# NiXie_tube_clock.net
KiCad netlist of a schematic drawn in Altium Designer
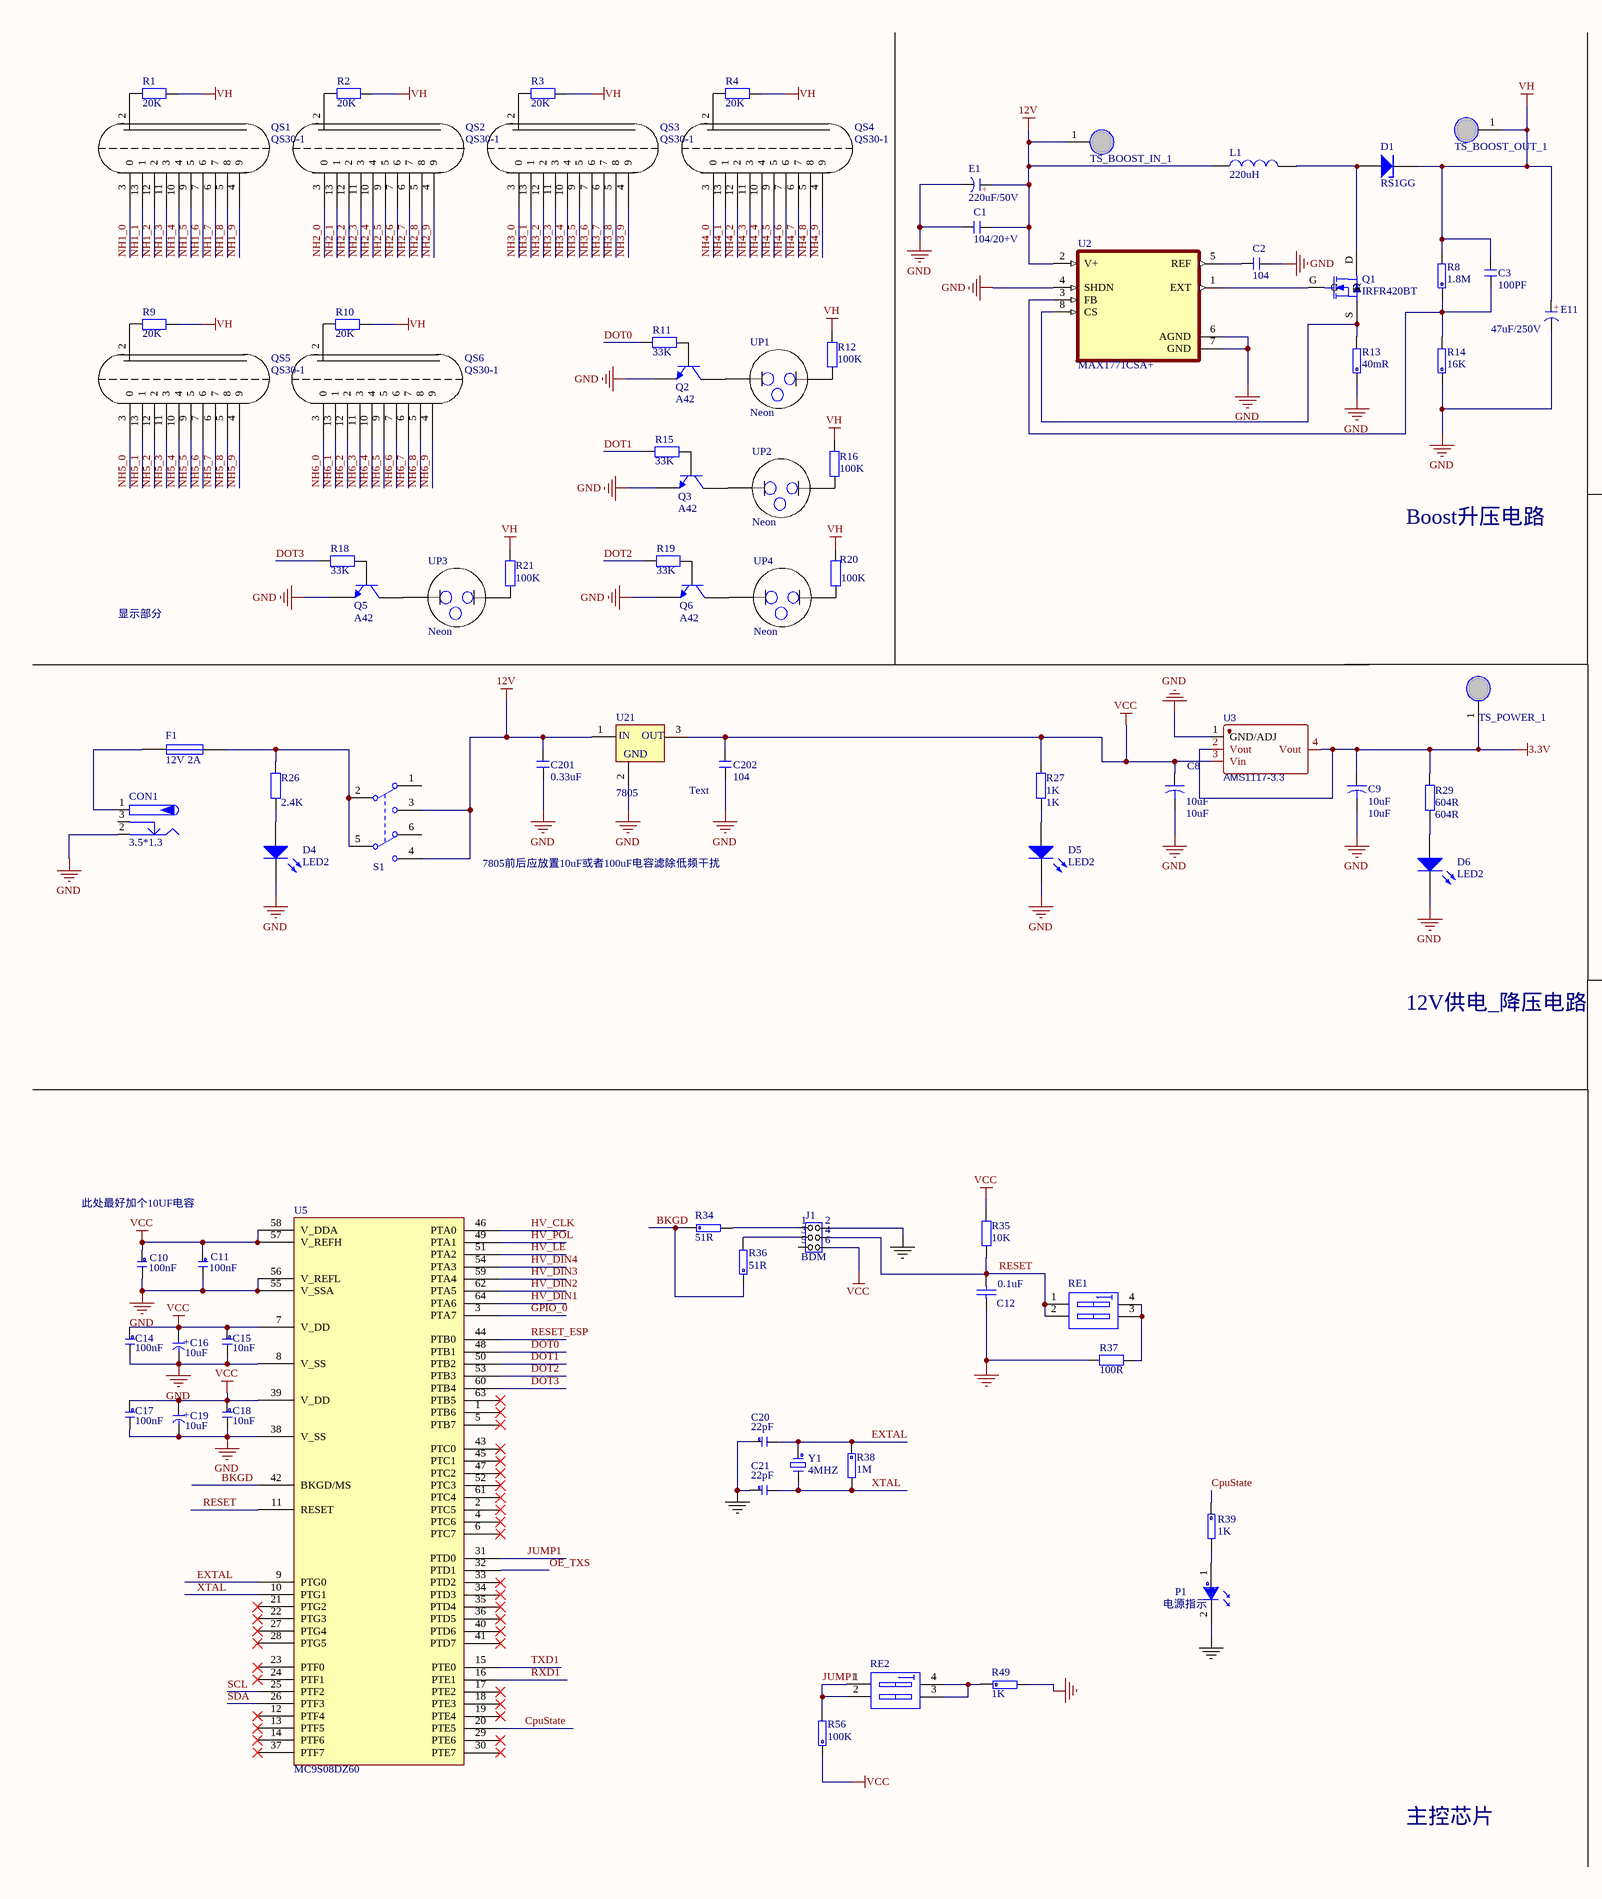
[diagram p0: NiXie_tube_clock.SchDoc, left]
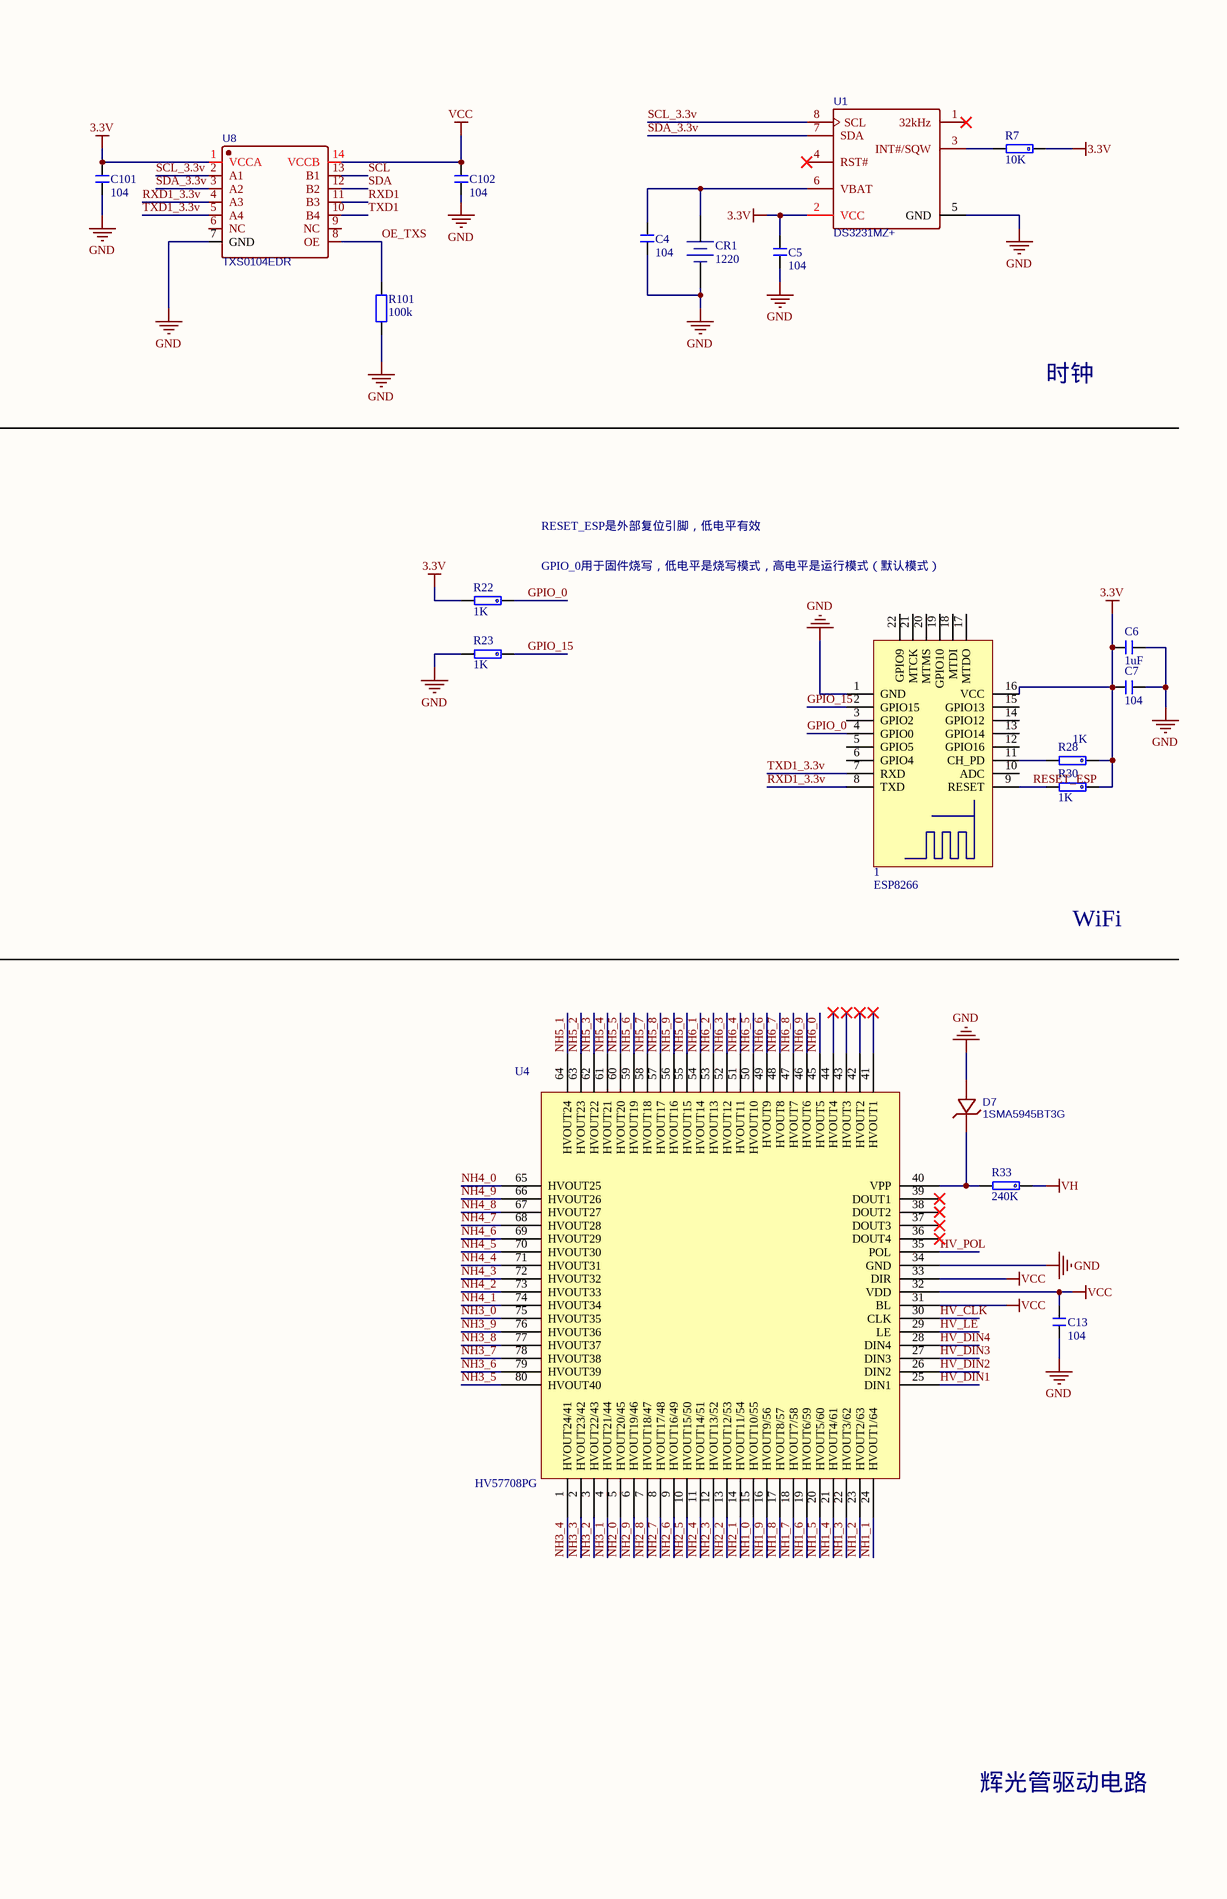
[diagram p1: NiXie_tube_clock.SchDoc, right]

(export (version "E")
  (design (tool "Eeschema 10.0.6"))
  (components
    (comp (ref "1") (value "ESP8266") (footprint "ESP8266") (libsource (lib "ESP8266V1.2") (part "ESP8266")))
    (comp (ref "C1")
      (value "104/20+V")
      (footprint "C 0805_L")
      (description "贴片电容")
      (libsource (lib "0.1 - 电阻-电容-电感") (part "C"))
    )
    (comp (ref "C2")
      (value "104")
      (footprint "C 0805_L")
      (description "贴片电容")
      (libsource (lib "0.1 - 电阻-电容-电感") (part "C"))
    )
    (comp (ref "C3")
      (value "100PF")
      (footprint "C 0805_L")
      (description "贴片电容")
      (libsource (lib "0.1 - 电阻-电容-电感") (part "C"))
    )
    (comp (ref "C4")
      (value "104")
      (footprint "C 0805_L")
      (description "贴片电容")
      (libsource (lib "0.1 - 电阻-电容-电感") (part "C"))
    )
    (comp (ref "C5")
      (value "104")
      (footprint "C 0805_L")
      (description "贴片电容")
      (libsource (lib "0.1 - 电阻-电容-电感") (part "C"))
    )
    (comp (ref "C6")
      (value "1uF")
      (footprint "C 0805_L")
      (description "贴片电容")
      (libsource (lib "0.1 - 电阻-电容-电感") (part "C"))
    )
    (comp (ref "C7")
      (value "104")
      (footprint "C 0805_L")
      (description "贴片电容")
      (libsource (lib "0.1 - 电阻-电容-电感") (part "C"))
    )
    (comp (ref "C8")
      (value "10uF")
      (footprint "CD B(3528)")
      (description "钽电容")
      (fields (field (name "ALTIUM_VALUE") "10uF") (field (name "PUBLISHER") "Altium Limited"))
      (libsource (lib "Miscellaneous Devices") (part "Cap2"))
    )
    (comp (ref "C9")
      (value "10uF")
      (footprint "CD B(3528)")
      (description "钽电容")
      (fields (field (name "ALTIUM_VALUE") "10uF") (field (name "PUBLISHER") "Altium Limited"))
      (libsource (lib "Miscellaneous Devices") (part "Cap2"))
    )
    (comp (ref "C10") (value "100nF") (footprint "R 0805_L") (libsource (lib "*") (part "CAP")))
    (comp (ref "C11") (value "100nF") (footprint "R 0805_L") (libsource (lib "*") (part "CAP")))
    (comp (ref "C12")
      (value "0.1uF")
      (footprint "R 0805_L")
      (description "Capacitor")
      (fields (field (name "PUBLISHER") "Altium Limited"))
      (libsource (lib "Miscellaneous Devices") (part "Cap"))
    )
    (comp (ref "C13")
      (value "104")
      (footprint "C 0805_L")
      (description "贴片电容")
      (libsource (lib "0.1 - 电阻-电容-电感") (part "C"))
    )
    (comp (ref "C14") (value "100nF") (footprint "R 0805_L") (libsource (lib "*") (part "CAP")))
    (comp (ref "C15") (value "10nF") (footprint "R 0805_L") (libsource (lib "*") (part "CAP")))
    (comp (ref "C16") (value "10uF") (footprint "CD B(3528)") (libsource (lib "*") (part "ELE-CAP")))
    (comp (ref "C17") (value "100nF") (footprint "R 0805_L") (libsource (lib "*") (part "CAP")))
    (comp (ref "C18") (value "10nF") (footprint "R 0805_L") (libsource (lib "*") (part "CAP")))
    (comp (ref "C19") (value "10uF") (footprint "CD B(3528)") (libsource (lib "*") (part "ELE-CAP")))
    (comp (ref "C20") (value "22pF") (footprint "R 0805_L") (libsource (lib "*") (part "CAP")))
    (comp (ref "C21") (value "22pF") (footprint "R 0805_L") (libsource (lib "*") (part "CAP")))
    (comp (ref "C101")
      (value "104")
      (footprint "C 0805_L")
      (description "贴片电容")
      (libsource (lib "0.1 - 电阻-电容-电感") (part "C"))
    )
    (comp (ref "C102")
      (value "104")
      (footprint "C 0805_L")
      (description "贴片电容")
      (libsource (lib "0.1 - 电阻-电容-电感") (part "C"))
    )
    (comp (ref "C201")
      (value "0.33uF")
      (footprint "C 0805_L")
      (description "贴片电容")
      (libsource (lib "0.1 - 电阻-电容-电感") (part "C"))
    )
    (comp (ref "C202")
      (value "104")
      (footprint "C 0805_L")
      (description "贴片电容")
      (libsource (lib "0.1 - 电阻-电容-电感") (part "C"))
    )
    (comp (ref "CON1")
      (value "3.5*1.3")
      (footprint "DC-005")
      (description "低压电源接口")
      (libsource (lib "0.8 - 以太网-音频-USB插座") (part "P-DC"))
    )
    (comp (ref "CR1")
      (value "1220")
      (footprint "CR1220_A")
      (description "微型电池")
      (libsource (lib "0.7 - 常用按键-开关-蜂鸣器-电池") (part "CR-3V"))
    )
    (comp (ref "D1")
      (value "RS1GG")
      (footprint "SMA")
      (description "Zener Diode")
      (libsource (lib "0.2 - 二极管-整流桥") (part "稳压二极管"))
    )
    (comp (ref "D4")
      (value "LED2")
      (footprint "LED 0805G")
      (description "Typical RED, GREEN, YELLOW, AMBER GaAs LED")
      (fields (field (name "PUBLISHER") "Altium Limited"))
      (libsource (lib "Miscellaneous Devices") (part "LED2"))
    )
    (comp (ref "D5")
      (value "LED2")
      (footprint "LED 0805G")
      (description "Typical RED, GREEN, YELLOW, AMBER GaAs LED")
      (fields (field (name "PUBLISHER") "Altium Limited"))
      (libsource (lib "Miscellaneous Devices") (part "LED2"))
    )
    (comp (ref "D6")
      (value "LED2")
      (footprint "LED 0805G")
      (description "Typical RED, GREEN, YELLOW, AMBER GaAs LED")
      (fields (field (name "PUBLISHER") "Altium Limited"))
      (libsource (lib "Miscellaneous Devices") (part "LED2"))
    )
    (comp (ref "D7")
      (value "1SMA5945BT3G")
      (footprint "SMA")
      (fields
        (field (name "BOM_SUPPLIER PART") "C94872")
        (field (name "BOM_MANUFACTURER PART") "1SMA5931BT3G")
        (field (name "CONTRIBUTOR") "LCSC")
      )
      (libsource (lib "ISMA5913BT3G") (part "1SMA5931BT3G"))
    )
    (comp (ref "E1")
      (value "220uF/50V")
      (footprint "CT 10*8 - C")
      (description "贴片固态电容")
      (libsource (lib "") (part "CS_SMD_1"))
    )
    (comp (ref "E11")
      (value "47uF/250V")
      (footprint "CAP 5.0*12.5*20")
      (description "贴片固态电容")
      (libsource (lib "0.1 - 电阻-电容-电感") (part "CS_SMD"))
    )
    (comp (ref "F1")
      (value "12V 2A")
      (footprint "FU 1206")
      (description "Fuse")
      (fields (field (name "PUBLISHER") "Altium Limited"))
      (libsource (lib "Miscellaneous Devices") (part "Fuse 1"))
    )
    (comp (ref "J1") (value "BDM") (footprint "PIN6") (libsource (lib "*") (part "BDM")))
    (comp (ref "L1")
      (value "220uH")
      (footprint "CDRH129")
      (description "小功率贴片电感")
      (libsource (lib "0.1 - 电阻-电容-电感") (part "L"))
    )
    (comp (ref "P1") (value "电源指示") (footprint "LED 0805R") (libsource (lib "*") (part "LED")))
    (comp (ref "Q1")
      (value "IRFR420BT")
      (footprint "TO252")
      (description "N-Channel MOSFET")
      (libsource (lib "0.4 - 三极管-场效应管-可控硅") (part "MOSFET-N"))
    )
    (comp (ref "Q2")
      (value "A42")
      (footprint "SOT23")
      (description "NPN General Purpose Amplifier")
      (fields (field (name "PUBLISHER") "Altium Limited"))
      (libsource (lib "Miscellaneous Devices") (part "2N3904"))
    )
    (comp (ref "Q3")
      (value "A42")
      (footprint "SOT-23")
      (description "NPN General Purpose Amplifier")
      (fields (field (name "PUBLISHER") "Altium Limited"))
      (libsource (lib "Miscellaneous Devices") (part "2N3904"))
    )
    (comp (ref "Q5")
      (value "A42")
      (footprint "SOT-23")
      (description "NPN General Purpose Amplifier")
      (fields (field (name "PUBLISHER") "Altium Limited"))
      (libsource (lib "Miscellaneous Devices") (part "2N3904"))
    )
    (comp (ref "Q6")
      (value "A42")
      (footprint "SOT-23")
      (description "NPN General Purpose Amplifier")
      (fields (field (name "PUBLISHER") "Altium Limited"))
      (libsource (lib "Miscellaneous Devices") (part "2N3904"))
    )
    (comp (ref "QS1") (value "QS30-1") (footprint "QS30-1") (libsource (lib "SCH") (part "QS30-1")))
    (comp (ref "QS2") (value "QS30-1") (footprint "QS30-1") (libsource (lib "SCH") (part "QS30-1")))
    (comp (ref "QS3") (value "QS30-1") (footprint "QS30-1") (libsource (lib "SCH") (part "QS30-1")))
    (comp (ref "QS4") (value "QS30-1") (footprint "QS30-1") (libsource (lib "SCH") (part "QS30-1")))
    (comp (ref "QS5") (value "QS30-1") (footprint "QS30-1") (libsource (lib "SCH") (part "QS30-1")))
    (comp (ref "QS6") (value "QS30-1") (footprint "QS30-1") (libsource (lib "SCH") (part "QS30-1")))
    (comp (ref "R1")
      (value "20K")
      (footprint "R 0805_L")
      (description "Resistor")
      (fields (field (name "PUBLISHER") "Altium Limited"))
      (libsource (lib "Miscellaneous Devices") (part "Res2"))
    )
    (comp (ref "R2")
      (value "20K")
      (footprint "R 0805_L")
      (description "Resistor")
      (fields (field (name "PUBLISHER") "Altium Limited"))
      (libsource (lib "Miscellaneous Devices") (part "Res2"))
    )
    (comp (ref "R3")
      (value "20K")
      (footprint "R 0805_L")
      (description "Resistor")
      (fields (field (name "PUBLISHER") "Altium Limited"))
      (libsource (lib "Miscellaneous Devices") (part "Res2"))
    )
    (comp (ref "R4")
      (value "20K")
      (footprint "R 0805_L")
      (description "Resistor")
      (fields (field (name "PUBLISHER") "Altium Limited"))
      (libsource (lib "Miscellaneous Devices") (part "Res2"))
    )
    (comp (ref "R7") (value "10K") (footprint "R 0805_L") (libsource (lib "*") (part "RESISTANCE")))
    (comp (ref "R8") (value "1.8M") (footprint "R 0805_L") (libsource (lib "*") (part "RESISTANCE")))
    (comp (ref "R9")
      (value "20K")
      (footprint "R 0805_L")
      (description "Resistor")
      (fields (field (name "PUBLISHER") "Altium Limited"))
      (libsource (lib "Miscellaneous Devices") (part "Res2"))
    )
    (comp (ref "R10")
      (value "20K")
      (footprint "R 0805_L")
      (description "Resistor")
      (fields (field (name "PUBLISHER") "Altium Limited"))
      (libsource (lib "Miscellaneous Devices") (part "Res2"))
    )
    (comp (ref "R11")
      (value "33K")
      (footprint "R 0805_L")
      (description "Resistor")
      (fields (field (name "PUBLISHER") "Altium Limited"))
      (libsource (lib "Miscellaneous Devices") (part "Res2"))
    )
    (comp (ref "R12")
      (value "100K")
      (footprint "R 0805_L")
      (description "Resistor")
      (fields (field (name "PUBLISHER") "Altium Limited"))
      (libsource (lib "") (part "Res2_1"))
    )
    (comp (ref "R13") (value "40mR") (footprint "R 0805_L") (libsource (lib "*") (part "RESISTANCE")))
    (comp (ref "R14") (value "16K") (footprint "R 0805_L") (libsource (lib "*") (part "RESISTANCE")))
    (comp (ref "R15")
      (value "33K")
      (footprint "R 0805_L")
      (description "Resistor")
      (fields (field (name "PUBLISHER") "Altium Limited"))
      (libsource (lib "Miscellaneous Devices") (part "Res2"))
    )
    (comp (ref "R16")
      (value "100K")
      (footprint "R 0805_L")
      (description "Resistor")
      (fields (field (name "PUBLISHER") "Altium Limited"))
      (libsource (lib "") (part "Res2_1"))
    )
    (comp (ref "R18")
      (value "33K")
      (footprint "R 0805_L")
      (description "Resistor")
      (fields (field (name "PUBLISHER") "Altium Limited"))
      (libsource (lib "Miscellaneous Devices") (part "Res2"))
    )
    (comp (ref "R19")
      (value "33K")
      (footprint "R 0805_L")
      (description "Resistor")
      (fields (field (name "PUBLISHER") "Altium Limited"))
      (libsource (lib "Miscellaneous Devices") (part "Res2"))
    )
    (comp (ref "R20")
      (value "100K")
      (footprint "R 0805_L")
      (description "Resistor")
      (fields (field (name "PUBLISHER") "Altium Limited"))
      (libsource (lib "") (part "Res2_1"))
    )
    (comp (ref "R21")
      (value "100K")
      (footprint "R 0805_L")
      (description "Resistor")
      (fields (field (name "PUBLISHER") "Altium Limited"))
      (libsource (lib "") (part "Res2_1"))
    )
    (comp (ref "R22") (value "1K") (footprint "R 0805_L") (libsource (lib "*") (part "RESISTANCE")))
    (comp (ref "R23") (value "1K") (footprint "R 0805_L") (libsource (lib "*") (part "RESISTANCE")))
    (comp (ref "R26")
      (value "2.4K")
      (footprint "R 0805_L")
      (description "Resistor")
      (fields (field (name "PUBLISHER") "Altium Limited"))
      (libsource (lib "") (part "Res2_1"))
    )
    (comp (ref "R27")
      (value "1K")
      (footprint "R 0805_L")
      (description "Resistor")
      (fields (field (name "ALTIUM_VALUE") "1K") (field (name "PUBLISHER") "Altium Limited"))
      (libsource (lib "") (part "Res2_1"))
    )
    (comp (ref "R28") (value "1K") (footprint "R 0805_L") (libsource (lib "*") (part "RESISTANCE")))
    (comp (ref "R29")
      (value "604R")
      (footprint "R 0805_L")
      (description "Resistor")
      (fields (field (name "ALTIUM_VALUE") "604R") (field (name "PUBLISHER") "Altium Limited"))
      (libsource (lib "") (part "Res2_1"))
    )
    (comp (ref "R30") (value "1K") (footprint "R 0805_L") (libsource (lib "*") (part "RESISTANCE")))
    (comp (ref "R33") (value "240K") (footprint "R 0805_L") (libsource (lib "*") (part "RESISTANCE")))
    (comp (ref "R34") (value "51R") (footprint "R 0805_L") (libsource (lib "*") (part "RESISTANCE")))
    (comp (ref "R35")
      (value "10K")
      (footprint "R 0805_L")
      (description "Resistor")
      (fields (field (name "PUBLISHER") "Altium Limited"))
      (libsource (lib "") (part "Res2_2"))
    )
    (comp (ref "R36") (value "51R") (footprint "R 0805_L") (libsource (lib "*") (part "RESISTANCE")))
    (comp (ref "R37")
      (value "100R")
      (footprint "R 0805_L")
      (description "Resistor")
      (fields (field (name "PUBLISHER") "Altium Limited"))
      (libsource (lib "") (part "Res2_3"))
    )
    (comp (ref "R38") (value "1M") (footprint "R 0805_L") (libsource (lib "*") (part "RESISTANCE")))
    (comp (ref "R39") (value "1K") (footprint "R 0805_L") (libsource (lib "*") (part "RESISTANCE")))
    (comp (ref "R49") (value "1K") (footprint "R 0805_L") (libsource (lib "*") (part "RESISTANCE")))
    (comp (ref "R56") (value "100K") (footprint "R 0805_L") (libsource (lib "*") (part "RESISTANCE")))
    (comp (ref "R101")
      (value "100k")
      (footprint "R 0805_M")
      (description "贴片电阻")
      (libsource (lib "0.1 - 电阻-电容-电感") (part "R"))
    )
    (comp (ref "RE1")
      (value "SW DIP-2")
      (footprint "6MManjian")
      (description "DIP Switch, 2 Position, SPST")
      (fields (field (name "PUBLISHER") "Altium Limited"))
      (libsource (lib "Miscellaneous Devices") (part "SW DIP-2"))
    )
    (comp (ref "RE2")
      (value "SW DIP-2")
      (footprint "6MManjian")
      (description "DIP Switch, 2 Position, SPST")
      (fields (field (name "PUBLISHER") "Altium Limited"))
      (libsource (lib "Miscellaneous Devices") (part "SW DIP-2"))
    )
    (comp (ref "S1")
      (value "SK-22D02")
      (footprint "钮子开关6脚3档")
      (description "2路波动开关")
      (libsource (lib "0.7 - 常用按键-开关-蜂鸣器-电池") (part "SSW-2P"))
    )
    (comp (ref "TS_BOOST_IN_1")
      (value "12x16")
      (footprint "TP_ROUND")
      (description "触控弹簧")
      (libsource (lib "0.7 - 常用按键-开关-蜂鸣器-电池") (part "TTS"))
    )
    (comp (ref "TS_BOOST_OUT_1")
      (value "12x16")
      (footprint "TP_round")
      (description "触控弹簧")
      (libsource (lib "0.7 - 常用按键-开关-蜂鸣器-电池") (part "TTS"))
    )
    (comp (ref "TS_POWER_1")
      (value "12x16")
      (footprint "TP_round")
      (description "触控弹簧")
      (libsource (lib "0.7 - 常用按键-开关-蜂鸣器-电池") (part "TTS"))
    )
    (comp (ref "U1")
      (value "DS3231MZ+")
      (footprint "SOIC-8")
      (fields (field (name "BOM_SUPPLIER PART") "C107410"))
      (libsource (lib "DS3231MZ+") (part "DS3231MZ+"))
    )
    (comp (ref "U2")
      (value "MAX1771CSA+")
      (footprint "SOIC-8")
      (description "Boost, Buck-Boost Regulator Positive Output Step-Up, Step-Up/Step-Down DC-DC Controller IC 8-SOIC")
      (fields (field (name "MF") "Maxim Integrated"))
      (libsource (lib "MAX1771CSA_") (part "MAX1771CSA+"))
    )
    (comp (ref "U3")
      (value "AMS1117-3.3")
      (footprint "SOT-223-3_L6.5-W3.4-P2.30-LS7.0-BR")
      (fields (field (name "BOM_SUPPLIER PART") "C6186"))
      (libsource (lib "ams1117_3.3") (part "AMS1117-3.3"))
    )
    (comp (ref "U4")
      (value "HV57708PG")
      (footprint "QFP80P2390X1790X340-80N")
      (libsource (lib "HV577708PG") (part "HV57708PG"))
    )
    (comp (ref "U5")
      (value "MC9S08DZ60")
      (footprint "64-LQFP-10 - duplicate")
      (libsource (lib "*") (part "MC9S08DZ60"))
    )
    (comp (ref "U8")
      (value "TXS0104EDR")
      (footprint "TXS0104E")
      (fields (field (name "BOM_SUPPLIER PART") "C79342") (field (name "CONTRIBUTOR") "LCSC"))
      (libsource (lib "TXS0104E") (part "TXS0104EDR"))
    )
    (comp (ref "U21") (value "7805") (footprint "TO-220-78XX") (libsource (lib "信号采集模块(2)") (part "7805")))
    (comp (ref "UP1") (value "Neon") (footprint "Neon") (libsource (lib "SCH") (part "Neon")))
    (comp (ref "UP2") (value "Neon") (footprint "Neon") (libsource (lib "SCH") (part "Neon")))
    (comp (ref "UP3") (value "Neon") (footprint "Neon") (libsource (lib "SCH") (part "Neon")))
    (comp (ref "UP4") (value "Neon") (footprint "Neon") (libsource (lib "SCH") (part "Neon")))
    (comp (ref "Y1") (value "4MHZ") (footprint "4M2P") (libsource (lib "*") (part "CRYSTAL")))
  )
  (nets
    (net (code "1") (name "/BKGD") (class "Default")
      (node (ref "R34") (pin "1") (pinfunction "1_1") (pintype "passive"))
      (node (ref "R36") (pin "1") (pinfunction "1_1") (pintype "passive"))
      (node (ref "U5") (pin "42") (pinfunction "BKGD/MS_42") (pintype "passive"))
    )
    (net (code "2") (name "/CpuState") (class "Default")
      (node (ref "R39") (pin "1") (pinfunction "1_1") (pintype "passive"))
      (node (ref "U5") (pin "20") (pinfunction "PTE5_20") (pintype "passive"))
    )
    (net (code "3") (name "/DOT0") (class "Default")
      (node (ref "R11") (pin "1") (pinfunction "1_1") (pintype "passive"))
      (node (ref "U5") (pin "48") (pinfunction "PTB1_48") (pintype "passive"))
    )
    (net (code "4") (name "/DOT1") (class "Default")
      (node (ref "R15") (pin "1") (pinfunction "1_1") (pintype "passive"))
      (node (ref "U5") (pin "50") (pinfunction "PTB2_50") (pintype "passive"))
    )
    (net (code "5") (name "/DOT2") (class "Default")
      (node (ref "R19") (pin "1") (pinfunction "1_1") (pintype "passive"))
      (node (ref "U5") (pin "53") (pinfunction "PTB3_53") (pintype "passive"))
    )
    (net (code "6") (name "/DOT3") (class "Default")
      (node (ref "R18") (pin "1") (pinfunction "1_1") (pintype "passive"))
      (node (ref "U5") (pin "60") (pinfunction "PTB4_60") (pintype "passive"))
    )
    (net (code "7") (name "/EXTAL") (class "Default")
      (node (ref "C20") (pin "2") (pinfunction "2_2") (pintype "passive"))
      (node (ref "R38") (pin "1") (pinfunction "1_1") (pintype "passive"))
      (node (ref "U5") (pin "9") (pinfunction "PTG0_9") (pintype "passive"))
      (node (ref "Y1") (pin "1") (pinfunction "1_1") (pintype "passive"))
    )
    (net (code "8") (name "/GPIO_0") (class "Default")
      (node (ref "1") (pin "4") (pinfunction "GPIO0_4") (pintype "passive"))
      (node (ref "R22") (pin "1") (pinfunction "1_1") (pintype "passive"))
      (node (ref "U5") (pin "3") (pinfunction "PTA7_3") (pintype "passive"))
    )
    (net (code "9") (name "/GPIO_15") (class "Default")
      (node (ref "1") (pin "2") (pinfunction "GPIO15_2") (pintype "passive"))
      (node (ref "R23") (pin "1") (pinfunction "1_1") (pintype "passive"))
    )
    (net (code "10") (name "/HV_CLK") (class "Default")
      (node (ref "U4") (pin "30") (pinfunction "CLK_30") (pintype "passive"))
      (node (ref "U5") (pin "46") (pinfunction "PTA0_46") (pintype "passive"))
    )
    (net (code "11") (name "/HV_DIN1") (class "Default")
      (node (ref "U4") (pin "25") (pinfunction "DIN1_25") (pintype "passive"))
      (node (ref "U5") (pin "64") (pinfunction "PTA6_64") (pintype "passive"))
    )
    (net (code "12") (name "/HV_DIN2") (class "Default")
      (node (ref "U4") (pin "26") (pinfunction "DIN2_26") (pintype "passive"))
      (node (ref "U5") (pin "62") (pinfunction "PTA5_62") (pintype "passive"))
    )
    (net (code "13") (name "/HV_DIN3") (class "Default")
      (node (ref "U4") (pin "27") (pinfunction "DIN3_27") (pintype "passive"))
      (node (ref "U5") (pin "59") (pinfunction "PTA4_59") (pintype "passive"))
    )
    (net (code "14") (name "/HV_DIN4") (class "Default")
      (node (ref "U4") (pin "28") (pinfunction "DIN4_28") (pintype "passive"))
      (node (ref "U5") (pin "54") (pinfunction "PTA3_54") (pintype "passive"))
    )
    (net (code "15") (name "/HV_LE") (class "Default")
      (node (ref "U4") (pin "29") (pinfunction "LE_29") (pintype "passive"))
      (node (ref "U5") (pin "51") (pinfunction "PTA2_51") (pintype "passive"))
    )
    (net (code "16") (name "/HV_POL") (class "Default")
      (node (ref "U4") (pin "35") (pinfunction "POL_35") (pintype "passive"))
      (node (ref "U5") (pin "49") (pinfunction "PTA1_49") (pintype "passive"))
    )
    (net (code "17") (name "/JUMP1") (class "Default")
      (node (ref "R56") (pin "2") (pinfunction "2_2") (pintype "passive"))
      (node (ref "RE2") (pin "1") (pinfunction "A1_1") (pintype "passive"))
      (node (ref "RE2") (pin "2") (pinfunction "A2_2") (pintype "passive"))
      (node (ref "U5") (pin "31") (pinfunction "PTD0_31") (pintype "passive"))
    )
    (net (code "18") (name "/NH1_0") (class "Default")
      (node (ref "QS1") (pin "3") (pinfunction "0_3") (pintype "passive"))
      (node (ref "U4") (pin "15") (pinfunction "HVOUT10/55_15") (pintype "passive"))
    )
    (net (code "19") (name "/NH1_1") (class "Default")
      (node (ref "QS1") (pin "13") (pinfunction "1_13") (pintype "passive"))
      (node (ref "U4") (pin "24") (pinfunction "HVOUT1/64_24") (pintype "passive"))
    )
    (net (code "20") (name "/NH1_2") (class "Default")
      (node (ref "QS1") (pin "12") (pinfunction "2_12") (pintype "passive"))
      (node (ref "U4") (pin "23") (pinfunction "HVOUT2/63_23") (pintype "passive"))
    )
    (net (code "21") (name "/NH1_3") (class "Default")
      (node (ref "QS1") (pin "11") (pinfunction "3_11") (pintype "passive"))
      (node (ref "U4") (pin "22") (pinfunction "HVOUT3/62_22") (pintype "passive"))
    )
    (net (code "22") (name "/NH1_4") (class "Default")
      (node (ref "QS1") (pin "10") (pinfunction "4_10") (pintype "passive"))
      (node (ref "U4") (pin "21") (pinfunction "HVOUT4/61_21") (pintype "passive"))
    )
    (net (code "23") (name "/NH1_5") (class "Default")
      (node (ref "QS1") (pin "9") (pinfunction "5_9") (pintype "passive"))
      (node (ref "U4") (pin "20") (pinfunction "HVOUT5/60_20") (pintype "passive"))
    )
    (net (code "24") (name "/NH1_6") (class "Default")
      (node (ref "QS1") (pin "7") (pinfunction "6_7") (pintype "passive"))
      (node (ref "U4") (pin "19") (pinfunction "HVOUT6/59_19") (pintype "passive"))
    )
    (net (code "25") (name "/NH1_7") (class "Default")
      (node (ref "QS1") (pin "6") (pinfunction "7_6") (pintype "passive"))
      (node (ref "U4") (pin "18") (pinfunction "HVOUT7/58_18") (pintype "passive"))
    )
    (net (code "26") (name "/NH1_8") (class "Default")
      (node (ref "QS1") (pin "5") (pinfunction "8_5") (pintype "passive"))
      (node (ref "U4") (pin "17") (pinfunction "HVOUT8/57_17") (pintype "passive"))
    )
    (net (code "27") (name "/NH1_9") (class "Default")
      (node (ref "QS1") (pin "4") (pinfunction "9_4") (pintype "passive"))
      (node (ref "U4") (pin "16") (pinfunction "HVOUT9/56_16") (pintype "passive"))
    )
    (net (code "28") (name "/NH2_0") (class "Default")
      (node (ref "QS2") (pin "3") (pinfunction "0_3") (pintype "passive"))
      (node (ref "U4") (pin "5") (pinfunction "HVOUT20/45_5") (pintype "passive"))
    )
    (net (code "29") (name "/NH2_1") (class "Default")
      (node (ref "QS2") (pin "13") (pinfunction "1_13") (pintype "passive"))
      (node (ref "U4") (pin "14") (pinfunction "HVOUT11/54_14") (pintype "passive"))
    )
    (net (code "30") (name "/NH2_2") (class "Default")
      (node (ref "QS2") (pin "12") (pinfunction "2_12") (pintype "passive"))
      (node (ref "U4") (pin "13") (pinfunction "HVOUT12/53_13") (pintype "passive"))
    )
    (net (code "31") (name "/NH2_3") (class "Default")
      (node (ref "QS2") (pin "11") (pinfunction "3_11") (pintype "passive"))
      (node (ref "U4") (pin "12") (pinfunction "HVOUT13/52_12") (pintype "passive"))
    )
    (net (code "32") (name "/NH2_4") (class "Default")
      (node (ref "QS2") (pin "10") (pinfunction "4_10") (pintype "passive"))
      (node (ref "U4") (pin "11") (pinfunction "HVOUT14/51_11") (pintype "passive"))
    )
    (net (code "33") (name "/NH2_5") (class "Default")
      (node (ref "QS2") (pin "9") (pinfunction "5_9") (pintype "passive"))
      (node (ref "U4") (pin "10") (pinfunction "HVOUT15/50_10") (pintype "passive"))
    )
    (net (code "34") (name "/NH2_6") (class "Default")
      (node (ref "QS2") (pin "7") (pinfunction "6_7") (pintype "passive"))
      (node (ref "U4") (pin "9") (pinfunction "HVOUT16/49_9") (pintype "passive"))
    )
    (net (code "35") (name "/NH2_7") (class "Default")
      (node (ref "QS2") (pin "6") (pinfunction "7_6") (pintype "passive"))
      (node (ref "U4") (pin "8") (pinfunction "HVOUT17/48_8") (pintype "passive"))
    )
    (net (code "36") (name "/NH2_8") (class "Default")
      (node (ref "QS2") (pin "5") (pinfunction "8_5") (pintype "passive"))
      (node (ref "U4") (pin "7") (pinfunction "HVOUT18/47_7") (pintype "passive"))
    )
    (net (code "37") (name "/NH2_9") (class "Default")
      (node (ref "QS2") (pin "4") (pinfunction "9_4") (pintype "passive"))
      (node (ref "U4") (pin "6") (pinfunction "HVOUT19/46_6") (pintype "passive"))
    )
    (net (code "38") (name "/NH3_0") (class "Default")
      (node (ref "QS3") (pin "3") (pinfunction "0_3") (pintype "passive"))
      (node (ref "U4") (pin "75") (pinfunction "HVOUT35_75") (pintype "passive"))
    )
    (net (code "39") (name "/NH3_1") (class "Default")
      (node (ref "QS3") (pin "13") (pinfunction "1_13") (pintype "passive"))
      (node (ref "U4") (pin "4") (pinfunction "HVOUT21/44_4") (pintype "passive"))
    )
    (net (code "40") (name "/NH3_2") (class "Default")
      (node (ref "QS3") (pin "12") (pinfunction "2_12") (pintype "passive"))
      (node (ref "U4") (pin "3") (pinfunction "HVOUT22/43_3") (pintype "passive"))
    )
    (net (code "41") (name "/NH3_3") (class "Default")
      (node (ref "QS3") (pin "11") (pinfunction "3_11") (pintype "passive"))
      (node (ref "U4") (pin "2") (pinfunction "HVOUT23/42_2") (pintype "passive"))
    )
    (net (code "42") (name "/NH3_4") (class "Default")
      (node (ref "QS3") (pin "10") (pinfunction "4_10") (pintype "passive"))
      (node (ref "U4") (pin "1") (pinfunction "HVOUT24/41_1") (pintype "passive"))
    )
    (net (code "43") (name "/NH3_5") (class "Default")
      (node (ref "QS3") (pin "9") (pinfunction "5_9") (pintype "passive"))
      (node (ref "U4") (pin "80") (pinfunction "HVOUT40_80") (pintype "passive"))
    )
    (net (code "44") (name "/NH3_6") (class "Default")
      (node (ref "QS3") (pin "7") (pinfunction "6_7") (pintype "passive"))
      (node (ref "U4") (pin "79") (pinfunction "HVOUT39_79") (pintype "passive"))
    )
    (net (code "45") (name "/NH3_7") (class "Default")
      (node (ref "QS3") (pin "6") (pinfunction "7_6") (pintype "passive"))
      (node (ref "U4") (pin "78") (pinfunction "HVOUT38_78") (pintype "passive"))
    )
    (net (code "46") (name "/NH3_8") (class "Default")
      (node (ref "QS3") (pin "5") (pinfunction "8_5") (pintype "passive"))
      (node (ref "U4") (pin "77") (pinfunction "HVOUT37_77") (pintype "passive"))
    )
    (net (code "47") (name "/NH3_9") (class "Default")
      (node (ref "QS3") (pin "4") (pinfunction "9_4") (pintype "passive"))
      (node (ref "U4") (pin "76") (pinfunction "HVOUT36_76") (pintype "passive"))
    )
    (net (code "48") (name "/NH4_0") (class "Default")
      (node (ref "QS4") (pin "3") (pinfunction "0_3") (pintype "passive"))
      (node (ref "U4") (pin "65") (pinfunction "HVOUT25_65") (pintype "passive"))
    )
    (net (code "49") (name "/NH4_1") (class "Default")
      (node (ref "QS4") (pin "13") (pinfunction "1_13") (pintype "passive"))
      (node (ref "U4") (pin "74") (pinfunction "HVOUT34_74") (pintype "passive"))
    )
    (net (code "50") (name "/NH4_2") (class "Default")
      (node (ref "QS4") (pin "12") (pinfunction "2_12") (pintype "passive"))
      (node (ref "U4") (pin "73") (pinfunction "HVOUT33_73") (pintype "passive"))
    )
    (net (code "51") (name "/NH4_3") (class "Default")
      (node (ref "QS4") (pin "11") (pinfunction "3_11") (pintype "passive"))
      (node (ref "U4") (pin "72") (pinfunction "HVOUT32_72") (pintype "passive"))
    )
    (net (code "52") (name "/NH4_4") (class "Default")
      (node (ref "QS4") (pin "10") (pinfunction "4_10") (pintype "passive"))
      (node (ref "U4") (pin "71") (pinfunction "HVOUT31_71") (pintype "passive"))
    )
    (net (code "53") (name "/NH4_5") (class "Default")
      (node (ref "QS4") (pin "9") (pinfunction "5_9") (pintype "passive"))
      (node (ref "U4") (pin "70") (pinfunction "HVOUT30_70") (pintype "passive"))
    )
    (net (code "54") (name "/NH4_6") (class "Default")
      (node (ref "QS4") (pin "7") (pinfunction "6_7") (pintype "passive"))
      (node (ref "U4") (pin "69") (pinfunction "HVOUT29_69") (pintype "passive"))
    )
    (net (code "55") (name "/NH4_7") (class "Default")
      (node (ref "QS4") (pin "6") (pinfunction "7_6") (pintype "passive"))
      (node (ref "U4") (pin "68") (pinfunction "HVOUT28_68") (pintype "passive"))
    )
    (net (code "56") (name "/NH4_8") (class "Default")
      (node (ref "QS4") (pin "5") (pinfunction "8_5") (pintype "passive"))
      (node (ref "U4") (pin "67") (pinfunction "HVOUT27_67") (pintype "passive"))
    )
    (net (code "57") (name "/NH4_9") (class "Default")
      (node (ref "QS4") (pin "4") (pinfunction "9_4") (pintype "passive"))
      (node (ref "U4") (pin "66") (pinfunction "HVOUT26_66") (pintype "passive"))
    )
    (net (code "58") (name "/NH5_0") (class "Default")
      (node (ref "QS5") (pin "3") (pinfunction "0_3") (pintype "passive"))
      (node (ref "U4") (pin "55") (pinfunction "HVOUT15_55") (pintype "passive"))
    )
    (net (code "59") (name "/NH5_1") (class "Default")
      (node (ref "QS5") (pin "13") (pinfunction "1_13") (pintype "passive"))
      (node (ref "U4") (pin "64") (pinfunction "HVOUT24_64") (pintype "passive"))
    )
    (net (code "60") (name "/NH5_2") (class "Default")
      (node (ref "QS5") (pin "12") (pinfunction "2_12") (pintype "passive"))
      (node (ref "U4") (pin "63") (pinfunction "HVOUT23_63") (pintype "passive"))
    )
    (net (code "61") (name "/NH5_3") (class "Default")
      (node (ref "QS5") (pin "11") (pinfunction "3_11") (pintype "passive"))
      (node (ref "U4") (pin "62") (pinfunction "HVOUT22_62") (pintype "passive"))
    )
    (net (code "62") (name "/NH5_4") (class "Default")
      (node (ref "QS5") (pin "10") (pinfunction "4_10") (pintype "passive"))
      (node (ref "U4") (pin "61") (pinfunction "HVOUT21_61") (pintype "passive"))
    )
    (net (code "63") (name "/NH5_5") (class "Default")
      (node (ref "QS5") (pin "9") (pinfunction "5_9") (pintype "passive"))
      (node (ref "U4") (pin "60") (pinfunction "HVOUT20_60") (pintype "passive"))
    )
    (net (code "64") (name "/NH5_6") (class "Default")
      (node (ref "QS5") (pin "7") (pinfunction "6_7") (pintype "passive"))
      (node (ref "U4") (pin "59") (pinfunction "HVOUT19_59") (pintype "passive"))
    )
    (net (code "65") (name "/NH5_7") (class "Default")
      (node (ref "QS5") (pin "6") (pinfunction "7_6") (pintype "passive"))
      (node (ref "U4") (pin "58") (pinfunction "HVOUT18_58") (pintype "passive"))
    )
    (net (code "66") (name "/NH5_8") (class "Default")
      (node (ref "QS5") (pin "5") (pinfunction "8_5") (pintype "passive"))
      (node (ref "U4") (pin "57") (pinfunction "HVOUT17_57") (pintype "passive"))
    )
    (net (code "67") (name "/NH5_9") (class "Default")
      (node (ref "QS5") (pin "4") (pinfunction "9_4") (pintype "passive"))
      (node (ref "U4") (pin "56") (pinfunction "HVOUT16_56") (pintype "passive"))
    )
    (net (code "68") (name "/NH6_0") (class "Default")
      (node (ref "QS6") (pin "3") (pinfunction "0_3") (pintype "passive"))
      (node (ref "U4") (pin "45") (pinfunction "HVOUT5_45") (pintype "passive"))
    )
    (net (code "69") (name "/NH6_1") (class "Default")
      (node (ref "QS6") (pin "13") (pinfunction "1_13") (pintype "passive"))
      (node (ref "U4") (pin "54") (pinfunction "HVOUT14_54") (pintype "passive"))
    )
    (net (code "70") (name "/NH6_2") (class "Default")
      (node (ref "QS6") (pin "12") (pinfunction "2_12") (pintype "passive"))
      (node (ref "U4") (pin "53") (pinfunction "HVOUT13_53") (pintype "passive"))
    )
    (net (code "71") (name "/NH6_3") (class "Default")
      (node (ref "QS6") (pin "11") (pinfunction "3_11") (pintype "passive"))
      (node (ref "U4") (pin "52") (pinfunction "HVOUT12_52") (pintype "passive"))
    )
    (net (code "72") (name "/NH6_4") (class "Default")
      (node (ref "QS6") (pin "10") (pinfunction "4_10") (pintype "passive"))
      (node (ref "U4") (pin "51") (pinfunction "HVOUT11_51") (pintype "passive"))
    )
    (net (code "73") (name "/NH6_5") (class "Default")
      (node (ref "QS6") (pin "9") (pinfunction "5_9") (pintype "passive"))
      (node (ref "U4") (pin "50") (pinfunction "HVOUT10_50") (pintype "passive"))
    )
    (net (code "74") (name "/NH6_6") (class "Default")
      (node (ref "QS6") (pin "7") (pinfunction "6_7") (pintype "passive"))
      (node (ref "U4") (pin "49") (pinfunction "HVOUT9_49") (pintype "passive"))
    )
    (net (code "75") (name "/NH6_7") (class "Default")
      (node (ref "QS6") (pin "6") (pinfunction "7_6") (pintype "passive"))
      (node (ref "U4") (pin "48") (pinfunction "HVOUT8_48") (pintype "passive"))
    )
    (net (code "76") (name "/NH6_8") (class "Default")
      (node (ref "QS6") (pin "5") (pinfunction "8_5") (pintype "passive"))
      (node (ref "U4") (pin "47") (pinfunction "HVOUT7_47") (pintype "passive"))
    )
    (net (code "77") (name "/NH6_9") (class "Default")
      (node (ref "QS6") (pin "4") (pinfunction "9_4") (pintype "passive"))
      (node (ref "U4") (pin "46") (pinfunction "HVOUT6_46") (pintype "passive"))
    )
    (net (code "78") (name "/OE_TXS") (class "Default")
      (node (ref "R101") (pin "2") (pinfunction "2_2") (pintype "passive"))
      (node (ref "U5") (pin "32") (pinfunction "PTD1_32") (pintype "passive"))
      (node (ref "U8") (pin "8") (pinfunction "OE_8") (pintype "passive"))
    )
    (net (code "79") (name "/RESET") (class "Default")
      (node (ref "C12") (pin "2") (pinfunction "2_2") (pintype "passive"))
      (node (ref "J1") (pin "4") (pinfunction "4_4") (pintype "passive"))
      (node (ref "R35") (pin "1") (pinfunction "1_1") (pintype "passive"))
      (node (ref "RE1") (pin "1") (pinfunction "A1_1") (pintype "passive"))
      (node (ref "RE1") (pin "2") (pinfunction "A2_2") (pintype "passive"))
      (node (ref "U5") (pin "11") (pinfunction "RESET_11") (pintype "passive"))
    )
    (net (code "80") (name "/RESET_ESP") (class "Default")
      (node (ref "1") (pin "9") (pinfunction "RESET_9") (pintype "passive"))
      (node (ref "R30") (pin "2") (pinfunction "2_2") (pintype "passive"))
      (node (ref "U5") (pin "44") (pinfunction "PTB0_44") (pintype "passive"))
    )
    (net (code "81") (name "/RXD1") (class "Default")
      (node (ref "U5") (pin "16") (pinfunction "PTE1_16") (pintype "passive"))
      (node (ref "U8") (pin "11") (pinfunction "B3_11") (pintype "passive"))
    )
    (net (code "82") (name "/RXD1_3.3v") (class "Default")
      (node (ref "1") (pin "8") (pinfunction "TXD_8") (pintype "passive"))
      (node (ref "U8") (pin "4") (pinfunction "A3_4") (pintype "passive"))
    )
    (net (code "83") (name "/SCL") (class "Default")
      (node (ref "U5") (pin "25") (pinfunction "PTF2_25") (pintype "passive"))
      (node (ref "U8") (pin "13") (pinfunction "B1_13") (pintype "passive"))
    )
    (net (code "84") (name "/SCL_3.3v") (class "Default")
      (node (ref "U1") (pin "8") (pinfunction "SCL_8") (pintype "passive"))
      (node (ref "U8") (pin "2") (pinfunction "A1_2") (pintype "passive"))
    )
    (net (code "85") (name "/SDA") (class "Default")
      (node (ref "U5") (pin "26") (pinfunction "PTF3_26") (pintype "passive"))
      (node (ref "U8") (pin "12") (pinfunction "B2_12") (pintype "passive"))
    )
    (net (code "86") (name "/SDA_3.3v") (class "Default")
      (node (ref "U1") (pin "7") (pinfunction "SDA_7") (pintype "passive"))
      (node (ref "U8") (pin "3") (pinfunction "A2_3") (pintype "passive"))
    )
    (net (code "87") (name "/TXD1") (class "Default")
      (node (ref "U5") (pin "15") (pinfunction "PTE0_15") (pintype "passive"))
      (node (ref "U8") (pin "10") (pinfunction "B4_10") (pintype "passive"))
    )
    (net (code "88") (name "/TXD1_3.3v") (class "Default")
      (node (ref "1") (pin "7") (pinfunction "RXD_7") (pintype "passive"))
      (node (ref "U8") (pin "5") (pinfunction "A4_5") (pintype "passive"))
    )
    (net (code "89") (name "/XTAL") (class "Default")
      (node (ref "C21") (pin "2") (pinfunction "2_2") (pintype "passive"))
      (node (ref "R38") (pin "2") (pinfunction "2_2") (pintype "passive"))
      (node (ref "U5") (pin "10") (pinfunction "PTG1_10") (pintype "passive"))
      (node (ref "Y1") (pin "2") (pinfunction "2_2") (pintype "passive"))
    )
    (net (code "90") (name "3.3V") (class "Default")
      (node (ref "1") (pin "16") (pinfunction "VCC_16") (pintype "passive"))
      (node (ref "C101") (pin "1") (pinfunction "1_1") (pintype "passive"))
      (node (ref "C5") (pin "2") (pinfunction "2_2") (pintype "passive"))
      (node (ref "C6") (pin "1") (pinfunction "1_1") (pintype "passive"))
      (node (ref "C7") (pin "1") (pinfunction "1_1") (pintype "passive"))
      (node (ref "C9") (pin "1") (pinfunction "1_1") (pintype "passive"))
      (node (ref "R22") (pin "2") (pinfunction "2_2") (pintype "passive"))
      (node (ref "R28") (pin "1") (pinfunction "1_1") (pintype "passive"))
      (node (ref "R29") (pin "1") (pinfunction "1_1") (pintype "passive"))
      (node (ref "R30") (pin "1") (pinfunction "1_1") (pintype "passive"))
      (node (ref "R7") (pin "1") (pinfunction "1_1") (pintype "passive"))
      (node (ref "TS_POWER_1") (pin "1") (pinfunction "1_1") (pintype "passive"))
      (node (ref "U1") (pin "2") (pinfunction "VCC_2") (pintype "passive"))
      (node (ref "U3") (pin "2") (pinfunction "Vout_2") (pintype "passive"))
      (node (ref "U3") (pin "4") (pinfunction "Vout_4") (pintype "passive"))
      (node (ref "U8") (pin "1") (pinfunction "VCCA_1") (pintype "passive"))
    )
    (net (code "91") (name "12V") (class "Default")
      (node (ref "C1") (pin "1") (pinfunction "1_1") (pintype "passive"))
      (node (ref "C201") (pin "1") (pinfunction "1_1") (pintype "passive"))
      (node (ref "E1") (pin "1") (pinfunction "A_1") (pintype "passive"))
      (node (ref "L1") (pin "1") (pinfunction "1_1") (pintype "passive"))
      (node (ref "S1") (pin "3") (pinfunction "3_3") (pintype "passive"))
      (node (ref "S1") (pin "4") (pinfunction "4_4") (pintype "passive"))
      (node (ref "TS_BOOST_IN_1") (pin "1") (pinfunction "1_1") (pintype "passive"))
      (node (ref "U2") (pin "2") (pinfunction "V+_2") (pintype "input"))
      (node (ref "U21") (pin "1") (pinfunction "IN_1") (pintype "passive"))
    )
    (net (code "92") (name "GND") (class "Default")
      (node (ref "1") (pin "1") (pinfunction "GND_1") (pintype "open_emitter"))
      (node (ref "C1") (pin "2") (pinfunction "2_2") (pintype "passive"))
      (node (ref "C10") (pin "2") (pinfunction "2_2") (pintype "passive"))
      (node (ref "C101") (pin "2") (pinfunction "2_2") (pintype "passive"))
      (node (ref "C102") (pin "2") (pinfunction "2_2") (pintype "passive"))
      (node (ref "C11") (pin "2") (pinfunction "2_2") (pintype "passive"))
      (node (ref "C12") (pin "1") (pinfunction "1_1") (pintype "passive"))
      (node (ref "C13") (pin "1") (pinfunction "1_1") (pintype "passive"))
      (node (ref "C14") (pin "2") (pinfunction "2_2") (pintype "passive"))
      (node (ref "C15") (pin "2") (pinfunction "2_2") (pintype "passive"))
      (node (ref "C16") (pin "2") (pinfunction "2_2") (pintype "passive"))
      (node (ref "C17") (pin "2") (pinfunction "2_2") (pintype "passive"))
      (node (ref "C18") (pin "2") (pinfunction "2_2") (pintype "passive"))
      (node (ref "C19") (pin "2") (pinfunction "2_2") (pintype "passive"))
      (node (ref "C2") (pin "1") (pinfunction "1_1") (pintype "passive"))
      (node (ref "C20") (pin "1") (pinfunction "1_1") (pintype "passive"))
      (node (ref "C201") (pin "2") (pinfunction "2_2") (pintype "passive"))
      (node (ref "C202") (pin "2") (pinfunction "2_2") (pintype "passive"))
      (node (ref "C21") (pin "1") (pinfunction "1_1") (pintype "passive"))
      (node (ref "C4") (pin "1") (pinfunction "1_1") (pintype "passive"))
      (node (ref "C5") (pin "1") (pinfunction "1_1") (pintype "passive"))
      (node (ref "C6") (pin "2") (pinfunction "2_2") (pintype "passive"))
      (node (ref "C7") (pin "2") (pinfunction "2_2") (pintype "passive"))
      (node (ref "C8") (pin "2") (pinfunction "2_2") (pintype "passive"))
      (node (ref "C9") (pin "2") (pinfunction "2_2") (pintype "passive"))
      (node (ref "CON1") (pin "2") (pintype "power_in"))
      (node (ref "CR1") (pin "2") (pinfunction "DC-_2") (pintype "passive"))
      (node (ref "D4") (pin "2") (pinfunction "K_2") (pintype "passive"))
      (node (ref "D5") (pin "2") (pinfunction "K_2") (pintype "passive"))
      (node (ref "D6") (pin "2") (pinfunction "K_2") (pintype "passive"))
      (node (ref "D7") (pin "2") (pinfunction "A_2") (pintype "passive"))
      (node (ref "E1") (pin "2") (pinfunction "K_2") (pintype "passive"))
      (node (ref "E11") (pin "2") (pinfunction "K_2") (pintype "passive"))
      (node (ref "J1") (pin "2") (pinfunction "2_2") (pintype "passive"))
      (node (ref "P1") (pin "2") (pinfunction "2_2") (pintype "passive"))
      (node (ref "Q2") (pin "2") (pinfunction "E_2") (pintype "passive"))
      (node (ref "Q3") (pin "2") (pinfunction "E_2") (pintype "passive"))
      (node (ref "Q5") (pin "2") (pinfunction "E_2") (pintype "passive"))
      (node (ref "Q6") (pin "2") (pinfunction "E_2") (pintype "passive"))
      (node (ref "R101") (pin "1") (pinfunction "1_1") (pintype "passive"))
      (node (ref "R13") (pin "1") (pinfunction "1_1") (pintype "passive"))
      (node (ref "R14") (pin "1") (pinfunction "1_1") (pintype "passive"))
      (node (ref "R23") (pin "2") (pinfunction "2_2") (pintype "passive"))
      (node (ref "R37") (pin "2") (pinfunction "2_2") (pintype "passive"))
      (node (ref "R49") (pin "2") (pinfunction "2_2") (pintype "passive"))
      (node (ref "U1") (pin "5") (pinfunction "GND_5") (pintype "passive"))
      (node (ref "U2") (pin "4") (pinfunction "SHDN_4") (pintype "input"))
      (node (ref "U2") (pin "6") (pinfunction "AGND_6") (pintype "power_in"))
      (node (ref "U2") (pin "7") (pinfunction "GND_7") (pintype "power_in"))
      (node (ref "U21") (pin "2") (pinfunction "GND_2") (pintype "passive"))
      (node (ref "U3") (pin "1") (pinfunction "GND/ADJ_1") (pintype "passive"))
      (node (ref "U4") (pin "34") (pinfunction "GND_34") (pintype "passive"))
      (node (ref "U5") (pin "38") (pinfunction "V_SS_38") (pintype "passive"))
      (node (ref "U5") (pin "55") (pinfunction "V_SSA_55") (pintype "passive"))
      (node (ref "U5") (pin "56") (pinfunction "V_REFL_56") (pintype "passive"))
      (node (ref "U5") (pin "8") (pinfunction "V_SS_8") (pintype "passive"))
      (node (ref "U8") (pin "7") (pinfunction "GND_7") (pintype "passive"))
    )
    (net (code "93") (name "Net-(1-CH_PD)") (class "Default")
      (node (ref "1") (pin "11") (pinfunction "CH_PD_11") (pintype "passive"))
      (node (ref "R28") (pin "2") (pinfunction "2_2") (pintype "passive"))
    )
    (net (code "94") (name "Net-(CON1-Pad1)") (class "Default")
      (node (ref "CON1") (pin "1") (pintype "power_in"))
      (node (ref "F1") (pin "1") (pinfunction "1_1") (pintype "passive"))
    )
    (net (code "95") (name "Net-(CR1-DC+)") (class "Default")
      (node (ref "C4") (pin "2") (pinfunction "2_2") (pintype "passive"))
      (node (ref "CR1") (pin "1") (pinfunction "DC+_1") (pintype "passive"))
      (node (ref "U1") (pin "6") (pinfunction "VBAT_6") (pintype "passive"))
    )
    (net (code "96") (name "Net-(D1-A)") (class "Default")
      (node (ref "D1") (pin "1") (pinfunction "A_1") (pintype "passive"))
      (node (ref "L1") (pin "2") (pinfunction "2_2") (pintype "passive"))
      (node (ref "Q1") (pin "D") (pinfunction "D_D") (pintype "passive"))
    )
    (net (code "97") (name "Net-(D4-A)") (class "Default")
      (node (ref "D4") (pin "1") (pinfunction "A_1") (pintype "passive"))
      (node (ref "R26") (pin "2") (pinfunction "2_2") (pintype "passive"))
    )
    (net (code "98") (name "Net-(D5-A)") (class "Default")
      (node (ref "D5") (pin "1") (pinfunction "A_1") (pintype "passive"))
      (node (ref "R27") (pin "2") (pinfunction "2_2") (pintype "passive"))
    )
    (net (code "99") (name "Net-(D6-A)") (class "Default")
      (node (ref "D6") (pin "1") (pinfunction "A_1") (pintype "passive"))
      (node (ref "R29") (pin "2") (pinfunction "2_2") (pintype "passive"))
    )
    (net (code "100") (name "Net-(D7-K)") (class "Default")
      (node (ref "D7") (pin "1") (pinfunction "K_1") (pintype "passive"))
      (node (ref "R33") (pin "2") (pinfunction "2_2") (pintype "passive"))
      (node (ref "U4") (pin "40") (pinfunction "VPP_40") (pintype "passive"))
    )
    (net (code "101") (name "Net-(F1-Pad2)") (class "Default")
      (node (ref "F1") (pin "2") (pinfunction "2_2") (pintype "passive"))
      (node (ref "R26") (pin "1") (pinfunction "1_1") (pintype "passive"))
      (node (ref "S1") (pin "2") (pinfunction "2_2") (pintype "passive"))
      (node (ref "S1") (pin "5") (pinfunction "5_5") (pintype "passive"))
    )
    (net (code "102") (name "Net-(J1-Pad1)") (class "Default")
      (node (ref "J1") (pin "1") (pinfunction "1_1") (pintype "passive"))
      (node (ref "R34") (pin "2") (pinfunction "2_2") (pintype "passive"))
    )
    (net (code "103") (name "Net-(J1-Pad3)") (class "Default")
      (node (ref "J1") (pin "3") (pinfunction "3_3") (pintype "passive"))
      (node (ref "R36") (pin "2") (pinfunction "2_2") (pintype "passive"))
    )
    (net (code "104") (name "Net-(P1-Pad1)") (class "Default")
      (node (ref "P1") (pin "1") (pinfunction "1_1") (pintype "passive"))
      (node (ref "R39") (pin "2") (pinfunction "2_2") (pintype "passive"))
    )
    (net (code "105") (name "Net-(Q2-B)") (class "Default")
      (node (ref "Q2") (pin "1") (pinfunction "B_1") (pintype "passive"))
      (node (ref "R11") (pin "2") (pinfunction "2_2") (pintype "passive"))
    )
    (net (code "106") (name "Net-(Q2-C)") (class "Default")
      (node (ref "Q2") (pin "3") (pinfunction "C_3") (pintype "passive"))
      (node (ref "UP1") (pin "2") (pinfunction "2_2") (pintype "passive"))
    )
    (net (code "107") (name "Net-(Q3-B)") (class "Default")
      (node (ref "Q3") (pin "1") (pinfunction "B_1") (pintype "passive"))
      (node (ref "R15") (pin "2") (pinfunction "2_2") (pintype "passive"))
    )
    (net (code "108") (name "Net-(Q3-C)") (class "Default")
      (node (ref "Q3") (pin "3") (pinfunction "C_3") (pintype "passive"))
      (node (ref "UP2") (pin "2") (pinfunction "2_2") (pintype "passive"))
    )
    (net (code "109") (name "Net-(Q5-B)") (class "Default")
      (node (ref "Q5") (pin "1") (pinfunction "B_1") (pintype "passive"))
      (node (ref "R18") (pin "2") (pinfunction "2_2") (pintype "passive"))
    )
    (net (code "110") (name "Net-(Q5-C)") (class "Default")
      (node (ref "Q5") (pin "3") (pinfunction "C_3") (pintype "passive"))
      (node (ref "UP3") (pin "2") (pinfunction "2_2") (pintype "passive"))
    )
    (net (code "111") (name "Net-(Q6-B)") (class "Default")
      (node (ref "Q6") (pin "1") (pinfunction "B_1") (pintype "passive"))
      (node (ref "R19") (pin "2") (pinfunction "2_2") (pintype "passive"))
    )
    (net (code "112") (name "Net-(Q6-C)") (class "Default")
      (node (ref "Q6") (pin "3") (pinfunction "C_3") (pintype "passive"))
      (node (ref "UP4") (pin "2") (pinfunction "2_2") (pintype "passive"))
    )
    (net (code "113") (name "Net-(QS1-10)") (class "Default")
      (node (ref "QS1") (pin "2") (pinfunction "10_2") (pintype "passive"))
      (node (ref "R1") (pin "1") (pinfunction "1_1") (pintype "passive"))
    )
    (net (code "114") (name "Net-(QS2-10)") (class "Default")
      (node (ref "QS2") (pin "2") (pinfunction "10_2") (pintype "passive"))
      (node (ref "R2") (pin "1") (pinfunction "1_1") (pintype "passive"))
    )
    (net (code "115") (name "Net-(QS3-10)") (class "Default")
      (node (ref "QS3") (pin "2") (pinfunction "10_2") (pintype "passive"))
      (node (ref "R3") (pin "1") (pinfunction "1_1") (pintype "passive"))
    )
    (net (code "116") (name "Net-(QS4-10)") (class "Default")
      (node (ref "QS4") (pin "2") (pinfunction "10_2") (pintype "passive"))
      (node (ref "R4") (pin "1") (pinfunction "1_1") (pintype "passive"))
    )
    (net (code "117") (name "Net-(QS5-10)") (class "Default")
      (node (ref "QS5") (pin "2") (pinfunction "10_2") (pintype "passive"))
      (node (ref "R9") (pin "1") (pinfunction "1_1") (pintype "passive"))
    )
    (net (code "118") (name "Net-(QS6-10)") (class "Default")
      (node (ref "QS6") (pin "2") (pinfunction "10_2") (pintype "passive"))
      (node (ref "R10") (pin "1") (pinfunction "1_1") (pintype "passive"))
    )
    (net (code "119") (name "Net-(R12-Pad2)") (class "Default")
      (node (ref "R12") (pin "2") (pinfunction "2_2") (pintype "passive"))
      (node (ref "UP1") (pin "1") (pinfunction "1_1") (pintype "passive"))
    )
    (net (code "120") (name "Net-(R16-Pad2)") (class "Default")
      (node (ref "R16") (pin "2") (pinfunction "2_2") (pintype "passive"))
      (node (ref "UP2") (pin "1") (pinfunction "1_1") (pintype "passive"))
    )
    (net (code "121") (name "Net-(R20-Pad2)") (class "Default")
      (node (ref "R20") (pin "2") (pinfunction "2_2") (pintype "passive"))
      (node (ref "UP4") (pin "1") (pinfunction "1_1") (pintype "passive"))
    )
    (net (code "122") (name "Net-(R21-Pad2)") (class "Default")
      (node (ref "R21") (pin "2") (pinfunction "2_2") (pintype "passive"))
      (node (ref "UP3") (pin "1") (pinfunction "1_1") (pintype "passive"))
    )
    (net (code "123") (name "Net-(RE1-B1)") (class "Default")
      (node (ref "R37") (pin "1") (pinfunction "1_1") (pintype "passive"))
      (node (ref "RE1") (pin "3") (pinfunction "B2_3") (pintype "passive"))
      (node (ref "RE1") (pin "4") (pinfunction "B1_4") (pintype "passive"))
    )
    (net (code "124") (name "Net-(RE2-B1)") (class "Default")
      (node (ref "R49") (pin "1") (pinfunction "1_1") (pintype "passive"))
      (node (ref "RE2") (pin "3") (pinfunction "B2_3") (pintype "passive"))
      (node (ref "RE2") (pin "4") (pinfunction "B1_4") (pintype "passive"))
    )
    (net (code "125") (name "Net-(U1-INT#{slash}SQW)") (class "Default")
      (node (ref "R7") (pin "2") (pinfunction "2_2") (pintype "passive"))
      (node (ref "U1") (pin "3") (pinfunction "INT#/SQW_3") (pintype "passive"))
    )
    (net (code "126") (name "Net-(U2-CS)") (class "Default")
      (node (ref "Q1") (pin "S") (pinfunction "S_S") (pintype "passive"))
      (node (ref "R13") (pin "2") (pinfunction "2_2") (pintype "passive"))
      (node (ref "U2") (pin "8") (pinfunction "CS_8") (pintype "input"))
    )
    (net (code "127") (name "Net-(U2-EXT)") (class "Default")
      (node (ref "Q1") (pin "G") (pinfunction "G_G") (pintype "passive"))
      (node (ref "U2") (pin "1") (pinfunction "EXT_1") (pintype "output"))
    )
    (net (code "128") (name "Net-(U2-FB)") (class "Default")
      (node (ref "C3") (pin "1") (pinfunction "1_1") (pintype "passive"))
      (node (ref "R14") (pin "2") (pinfunction "2_2") (pintype "passive"))
      (node (ref "R8") (pin "1") (pinfunction "1_1") (pintype "passive"))
      (node (ref "U2") (pin "3") (pinfunction "FB_3") (pintype "input"))
    )
    (net (code "129") (name "Net-(U2-REF)") (class "Default")
      (node (ref "C2") (pin "2") (pinfunction "2_2") (pintype "passive"))
      (node (ref "U2") (pin "5") (pinfunction "REF_5") (pintype "output"))
    )
    (net (code "130") (name "VCC") (class "Default")
      (node (ref "C10") (pin "1") (pinfunction "1_1") (pintype "passive"))
      (node (ref "C102") (pin "1") (pinfunction "1_1") (pintype "passive"))
      (node (ref "C11") (pin "1") (pinfunction "1_1") (pintype "passive"))
      (node (ref "C13") (pin "2") (pinfunction "2_2") (pintype "passive"))
      (node (ref "C14") (pin "1") (pinfunction "1_1") (pintype "passive"))
      (node (ref "C15") (pin "1") (pinfunction "1_1") (pintype "passive"))
      (node (ref "C16") (pin "1") (pinfunction "1_1") (pintype "passive"))
      (node (ref "C17") (pin "1") (pinfunction "1_1") (pintype "passive"))
      (node (ref "C18") (pin "1") (pinfunction "1_1") (pintype "passive"))
      (node (ref "C19") (pin "1") (pinfunction "1_1") (pintype "passive"))
      (node (ref "C202") (pin "1") (pinfunction "1_1") (pintype "passive"))
      (node (ref "C8") (pin "1") (pinfunction "1_1") (pintype "passive"))
      (node (ref "J1") (pin "6") (pinfunction "6_6") (pintype "passive"))
      (node (ref "R27") (pin "1") (pinfunction "1_1") (pintype "passive"))
      (node (ref "R35") (pin "2") (pinfunction "2_2") (pintype "passive"))
      (node (ref "R56") (pin "1") (pinfunction "1_1") (pintype "passive"))
      (node (ref "U21") (pin "3") (pinfunction "OUT_3") (pintype "passive"))
      (node (ref "U3") (pin "3") (pinfunction "Vin_3") (pintype "passive"))
      (node (ref "U4") (pin "31") (pinfunction "BL_31") (pintype "passive"))
      (node (ref "U4") (pin "32") (pinfunction "VDD_32") (pintype "passive"))
      (node (ref "U4") (pin "33") (pinfunction "DIR_33") (pintype "passive"))
      (node (ref "U5") (pin "39") (pinfunction "V_DD_39") (pintype "passive"))
      (node (ref "U5") (pin "57") (pinfunction "V_REFH_57") (pintype "passive"))
      (node (ref "U5") (pin "58") (pinfunction "V_DDA_58") (pintype "passive"))
      (node (ref "U5") (pin "7") (pinfunction "V_DD_7") (pintype "passive"))
      (node (ref "U8") (pin "14") (pinfunction "VCCB_14") (pintype "passive"))
    )
    (net (code "131") (name "VH") (class "Default")
      (node (ref "C3") (pin "2") (pinfunction "2_2") (pintype "passive"))
      (node (ref "D1") (pin "2") (pinfunction "K_2") (pintype "passive"))
      (node (ref "E11") (pin "1") (pinfunction "A_1") (pintype "passive"))
      (node (ref "R1") (pin "2") (pinfunction "2_2") (pintype "passive"))
      (node (ref "R10") (pin "2") (pinfunction "2_2") (pintype "passive"))
      (node (ref "R12") (pin "1") (pinfunction "1_1") (pintype "passive"))
      (node (ref "R16") (pin "1") (pinfunction "1_1") (pintype "passive"))
      (node (ref "R2") (pin "2") (pinfunction "2_2") (pintype "passive"))
      (node (ref "R20") (pin "1") (pinfunction "1_1") (pintype "passive"))
      (node (ref "R21") (pin "1") (pinfunction "1_1") (pintype "passive"))
      (node (ref "R3") (pin "2") (pinfunction "2_2") (pintype "passive"))
      (node (ref "R33") (pin "1") (pinfunction "1_1") (pintype "passive"))
      (node (ref "R4") (pin "2") (pinfunction "2_2") (pintype "passive"))
      (node (ref "R8") (pin "2") (pinfunction "2_2") (pintype "passive"))
      (node (ref "R9") (pin "2") (pinfunction "2_2") (pintype "passive"))
      (node (ref "TS_BOOST_OUT_1") (pin "1") (pinfunction "1_1") (pintype "passive"))
    )
    (net (code "132") (name "unconnected-(1-ADC-Pad10)") (class "Default")
      (node (ref "1") (pin "10") (pinfunction "ADC_10") (pintype "passive"))
    )
    (net (code "133") (name "unconnected-(1-GPIO2-Pad3)") (class "Default")
      (node (ref "1") (pin "3") (pinfunction "GPIO2_3") (pintype "passive"))
    )
    (net (code "134") (name "unconnected-(1-GPIO4-Pad6)") (class "Default")
      (node (ref "1") (pin "6") (pinfunction "GPIO4_6") (pintype "passive"))
    )
    (net (code "135") (name "unconnected-(1-GPIO5-Pad5)") (class "Default")
      (node (ref "1") (pin "5") (pinfunction "GPIO5_5") (pintype "passive"))
    )
    (net (code "136") (name "unconnected-(1-GPIO9-Pad22)") (class "Default")
      (node (ref "1") (pin "22") (pinfunction "GPIO9_22") (pintype "passive"))
    )
    (net (code "137") (name "unconnected-(1-GPIO10-Pad19)") (class "Default")
      (node (ref "1") (pin "19") (pinfunction "GPIO10_19") (pintype "passive"))
    )
    (net (code "138") (name "unconnected-(1-GPIO12-Pad14)") (class "Default")
      (node (ref "1") (pin "14") (pinfunction "GPIO12_14") (pintype "passive"))
    )
    (net (code "139") (name "unconnected-(1-GPIO13-Pad15)") (class "Default")
      (node (ref "1") (pin "15") (pinfunction "GPIO13_15") (pintype "passive"))
    )
    (net (code "140") (name "unconnected-(1-GPIO14-Pad13)") (class "Default")
      (node (ref "1") (pin "13") (pinfunction "GPIO14_13") (pintype "passive"))
    )
    (net (code "141") (name "unconnected-(1-GPIO16-Pad12)") (class "Default")
      (node (ref "1") (pin "12") (pinfunction "GPIO16_12") (pintype "passive"))
    )
    (net (code "142") (name "unconnected-(1-MTCK-Pad21)") (class "Default")
      (node (ref "1") (pin "21") (pinfunction "MTCK_21") (pintype "passive"))
    )
    (net (code "143") (name "unconnected-(1-MTDI-Pad18)") (class "Default")
      (node (ref "1") (pin "18") (pinfunction "MTDI_18") (pintype "passive"))
    )
    (net (code "144") (name "unconnected-(1-MTDO-Pad17)") (class "Default")
      (node (ref "1") (pin "17") (pinfunction "MTDO_17") (pintype "passive"))
    )
    (net (code "145") (name "unconnected-(1-MTMS-Pad20)") (class "Default")
      (node (ref "1") (pin "20") (pinfunction "MTMS_20") (pintype "passive"))
    )
    (net (code "146") (name "unconnected-(CON1-Pad3)") (class "Default")
      (node (ref "CON1") (pin "3") (pintype "power_in"))
    )
    (net (code "147") (name "unconnected-(J1-Pad5)") (class "Default")
      (node (ref "J1") (pin "5") (pinfunction "5_5") (pintype "passive"))
    )
    (net (code "148") (name "unconnected-(S1-Pad1)") (class "Default")
      (node (ref "S1") (pin "1") (pinfunction "1_1") (pintype "passive"))
    )
    (net (code "149") (name "unconnected-(S1-Pad6)") (class "Default")
      (node (ref "S1") (pin "6") (pinfunction "6_6") (pintype "passive"))
    )
    (net (code "150") (name "unconnected-(U1-32kHz-Pad1)") (class "Default")
      (node (ref "U1") (pin "1") (pinfunction "32kHz_1") (pintype "passive+no_connect"))
    )
    (net (code "151") (name "unconnected-(U1-RST#-Pad4)") (class "Default")
      (node (ref "U1") (pin "4") (pinfunction "RST#_4") (pintype "passive+no_connect"))
    )
    (net (code "152") (name "unconnected-(U4-DOUT1-Pad39)") (class "Default")
      (node (ref "U4") (pin "39") (pinfunction "DOUT1_39") (pintype "passive+no_connect"))
    )
    (net (code "153") (name "unconnected-(U4-DOUT2-Pad38)") (class "Default")
      (node (ref "U4") (pin "38") (pinfunction "DOUT2_38") (pintype "passive+no_connect"))
    )
    (net (code "154") (name "unconnected-(U4-DOUT3-Pad37)") (class "Default")
      (node (ref "U4") (pin "37") (pinfunction "DOUT3_37") (pintype "passive+no_connect"))
    )
    (net (code "155") (name "unconnected-(U4-DOUT4-Pad36)") (class "Default")
      (node (ref "U4") (pin "36") (pinfunction "DOUT4_36") (pintype "passive+no_connect"))
    )
    (net (code "156") (name "unconnected-(U4-HVOUT1-Pad41)") (class "Default")
      (node (ref "U4") (pin "41") (pinfunction "HVOUT1_41") (pintype "passive+no_connect"))
    )
    (net (code "157") (name "unconnected-(U4-HVOUT2-Pad42)") (class "Default")
      (node (ref "U4") (pin "42") (pinfunction "HVOUT2_42") (pintype "passive+no_connect"))
    )
    (net (code "158") (name "unconnected-(U4-HVOUT3-Pad43)") (class "Default")
      (node (ref "U4") (pin "43") (pinfunction "HVOUT3_43") (pintype "passive+no_connect"))
    )
    (net (code "159") (name "unconnected-(U4-HVOUT4-Pad44)") (class "Default")
      (node (ref "U4") (pin "44") (pinfunction "HVOUT4_44") (pintype "passive+no_connect"))
    )
    (net (code "160") (name "unconnected-(U5-PTB5-Pad63)") (class "Default")
      (node (ref "U5") (pin "63") (pinfunction "PTB5_63") (pintype "passive+no_connect"))
    )
    (net (code "161") (name "unconnected-(U5-PTB6-Pad1)") (class "Default")
      (node (ref "U5") (pin "1") (pinfunction "PTB6_1") (pintype "passive+no_connect"))
    )
    (net (code "162") (name "unconnected-(U5-PTB7-Pad5)") (class "Default")
      (node (ref "U5") (pin "5") (pinfunction "PTB7_5") (pintype "passive+no_connect"))
    )
    (net (code "163") (name "unconnected-(U5-PTC0-Pad43)") (class "Default")
      (node (ref "U5") (pin "43") (pinfunction "PTC0_43") (pintype "passive+no_connect"))
    )
    (net (code "164") (name "unconnected-(U5-PTC1-Pad45)") (class "Default")
      (node (ref "U5") (pin "45") (pinfunction "PTC1_45") (pintype "passive+no_connect"))
    )
    (net (code "165") (name "unconnected-(U5-PTC2-Pad47)") (class "Default")
      (node (ref "U5") (pin "47") (pinfunction "PTC2_47") (pintype "passive+no_connect"))
    )
    (net (code "166") (name "unconnected-(U5-PTC3-Pad52)") (class "Default")
      (node (ref "U5") (pin "52") (pinfunction "PTC3_52") (pintype "passive+no_connect"))
    )
    (net (code "167") (name "unconnected-(U5-PTC4-Pad61)") (class "Default")
      (node (ref "U5") (pin "61") (pinfunction "PTC4_61") (pintype "passive+no_connect"))
    )
    (net (code "168") (name "unconnected-(U5-PTC5-Pad2)") (class "Default")
      (node (ref "U5") (pin "2") (pinfunction "PTC5_2") (pintype "passive+no_connect"))
    )
    (net (code "169") (name "unconnected-(U5-PTC6-Pad4)") (class "Default")
      (node (ref "U5") (pin "4") (pinfunction "PTC6_4") (pintype "passive+no_connect"))
    )
    (net (code "170") (name "unconnected-(U5-PTC7-Pad6)") (class "Default")
      (node (ref "U5") (pin "6") (pinfunction "PTC7_6") (pintype "passive+no_connect"))
    )
    (net (code "171") (name "unconnected-(U5-PTD2-Pad33)") (class "Default")
      (node (ref "U5") (pin "33") (pinfunction "PTD2_33") (pintype "passive+no_connect"))
    )
    (net (code "172") (name "unconnected-(U5-PTD3-Pad34)") (class "Default")
      (node (ref "U5") (pin "34") (pinfunction "PTD3_34") (pintype "passive+no_connect"))
    )
    (net (code "173") (name "unconnected-(U5-PTD4-Pad35)") (class "Default")
      (node (ref "U5") (pin "35") (pinfunction "PTD4_35") (pintype "passive+no_connect"))
    )
    (net (code "174") (name "unconnected-(U5-PTD5-Pad36)") (class "Default")
      (node (ref "U5") (pin "36") (pinfunction "PTD5_36") (pintype "passive+no_connect"))
    )
    (net (code "175") (name "unconnected-(U5-PTD6-Pad40)") (class "Default")
      (node (ref "U5") (pin "40") (pinfunction "PTD6_40") (pintype "passive+no_connect"))
    )
    (net (code "176") (name "unconnected-(U5-PTD7-Pad41)") (class "Default")
      (node (ref "U5") (pin "41") (pinfunction "PTD7_41") (pintype "passive+no_connect"))
    )
    (net (code "177") (name "unconnected-(U5-PTE2-Pad17)") (class "Default")
      (node (ref "U5") (pin "17") (pinfunction "PTE2_17") (pintype "passive+no_connect"))
    )
    (net (code "178") (name "unconnected-(U5-PTE3-Pad18)") (class "Default")
      (node (ref "U5") (pin "18") (pinfunction "PTE3_18") (pintype "passive+no_connect"))
    )
    (net (code "179") (name "unconnected-(U5-PTE4-Pad19)") (class "Default")
      (node (ref "U5") (pin "19") (pinfunction "PTE4_19") (pintype "passive+no_connect"))
    )
    (net (code "180") (name "unconnected-(U5-PTE6-Pad29)") (class "Default")
      (node (ref "U5") (pin "29") (pinfunction "PTE6_29") (pintype "passive+no_connect"))
    )
    (net (code "181") (name "unconnected-(U5-PTE7-Pad30)") (class "Default")
      (node (ref "U5") (pin "30") (pinfunction "PTE7_30") (pintype "passive+no_connect"))
    )
    (net (code "182") (name "unconnected-(U5-PTF0-Pad23)") (class "Default")
      (node (ref "U5") (pin "23") (pinfunction "PTF0_23") (pintype "passive+no_connect"))
    )
    (net (code "183") (name "unconnected-(U5-PTF1-Pad24)") (class "Default")
      (node (ref "U5") (pin "24") (pinfunction "PTF1_24") (pintype "passive+no_connect"))
    )
    (net (code "184") (name "unconnected-(U5-PTF4-Pad12)") (class "Default")
      (node (ref "U5") (pin "12") (pinfunction "PTF4_12") (pintype "passive+no_connect"))
    )
    (net (code "185") (name "unconnected-(U5-PTF5-Pad13)") (class "Default")
      (node (ref "U5") (pin "13") (pinfunction "PTF5_13") (pintype "passive+no_connect"))
    )
    (net (code "186") (name "unconnected-(U5-PTF6-Pad14)") (class "Default")
      (node (ref "U5") (pin "14") (pinfunction "PTF6_14") (pintype "passive+no_connect"))
    )
    (net (code "187") (name "unconnected-(U5-PTF7-Pad37)") (class "Default")
      (node (ref "U5") (pin "37") (pinfunction "PTF7_37") (pintype "passive+no_connect"))
    )
    (net (code "188") (name "unconnected-(U5-PTG2-Pad21)") (class "Default")
      (node (ref "U5") (pin "21") (pinfunction "PTG2_21") (pintype "passive+no_connect"))
    )
    (net (code "189") (name "unconnected-(U5-PTG3-Pad22)") (class "Default")
      (node (ref "U5") (pin "22") (pinfunction "PTG3_22") (pintype "passive+no_connect"))
    )
    (net (code "190") (name "unconnected-(U5-PTG4-Pad27)") (class "Default")
      (node (ref "U5") (pin "27") (pinfunction "PTG4_27") (pintype "passive+no_connect"))
    )
    (net (code "191") (name "unconnected-(U5-PTG5-Pad28)") (class "Default")
      (node (ref "U5") (pin "28") (pinfunction "PTG5_28") (pintype "passive+no_connect"))
    )
    (net (code "192") (name "unconnected-(U8-NC-Pad6)") (class "Default")
      (node (ref "U8") (pin "6") (pinfunction "NC_6") (pintype "passive"))
    )
    (net (code "193") (name "unconnected-(U8-NC-Pad9)") (class "Default")
      (node (ref "U8") (pin "9") (pinfunction "NC_9") (pintype "passive"))
    )
  )
)
